# PLD_Sensors_AVR_Interface.net
KiCad netlist of a schematic drawn in Altium Designer
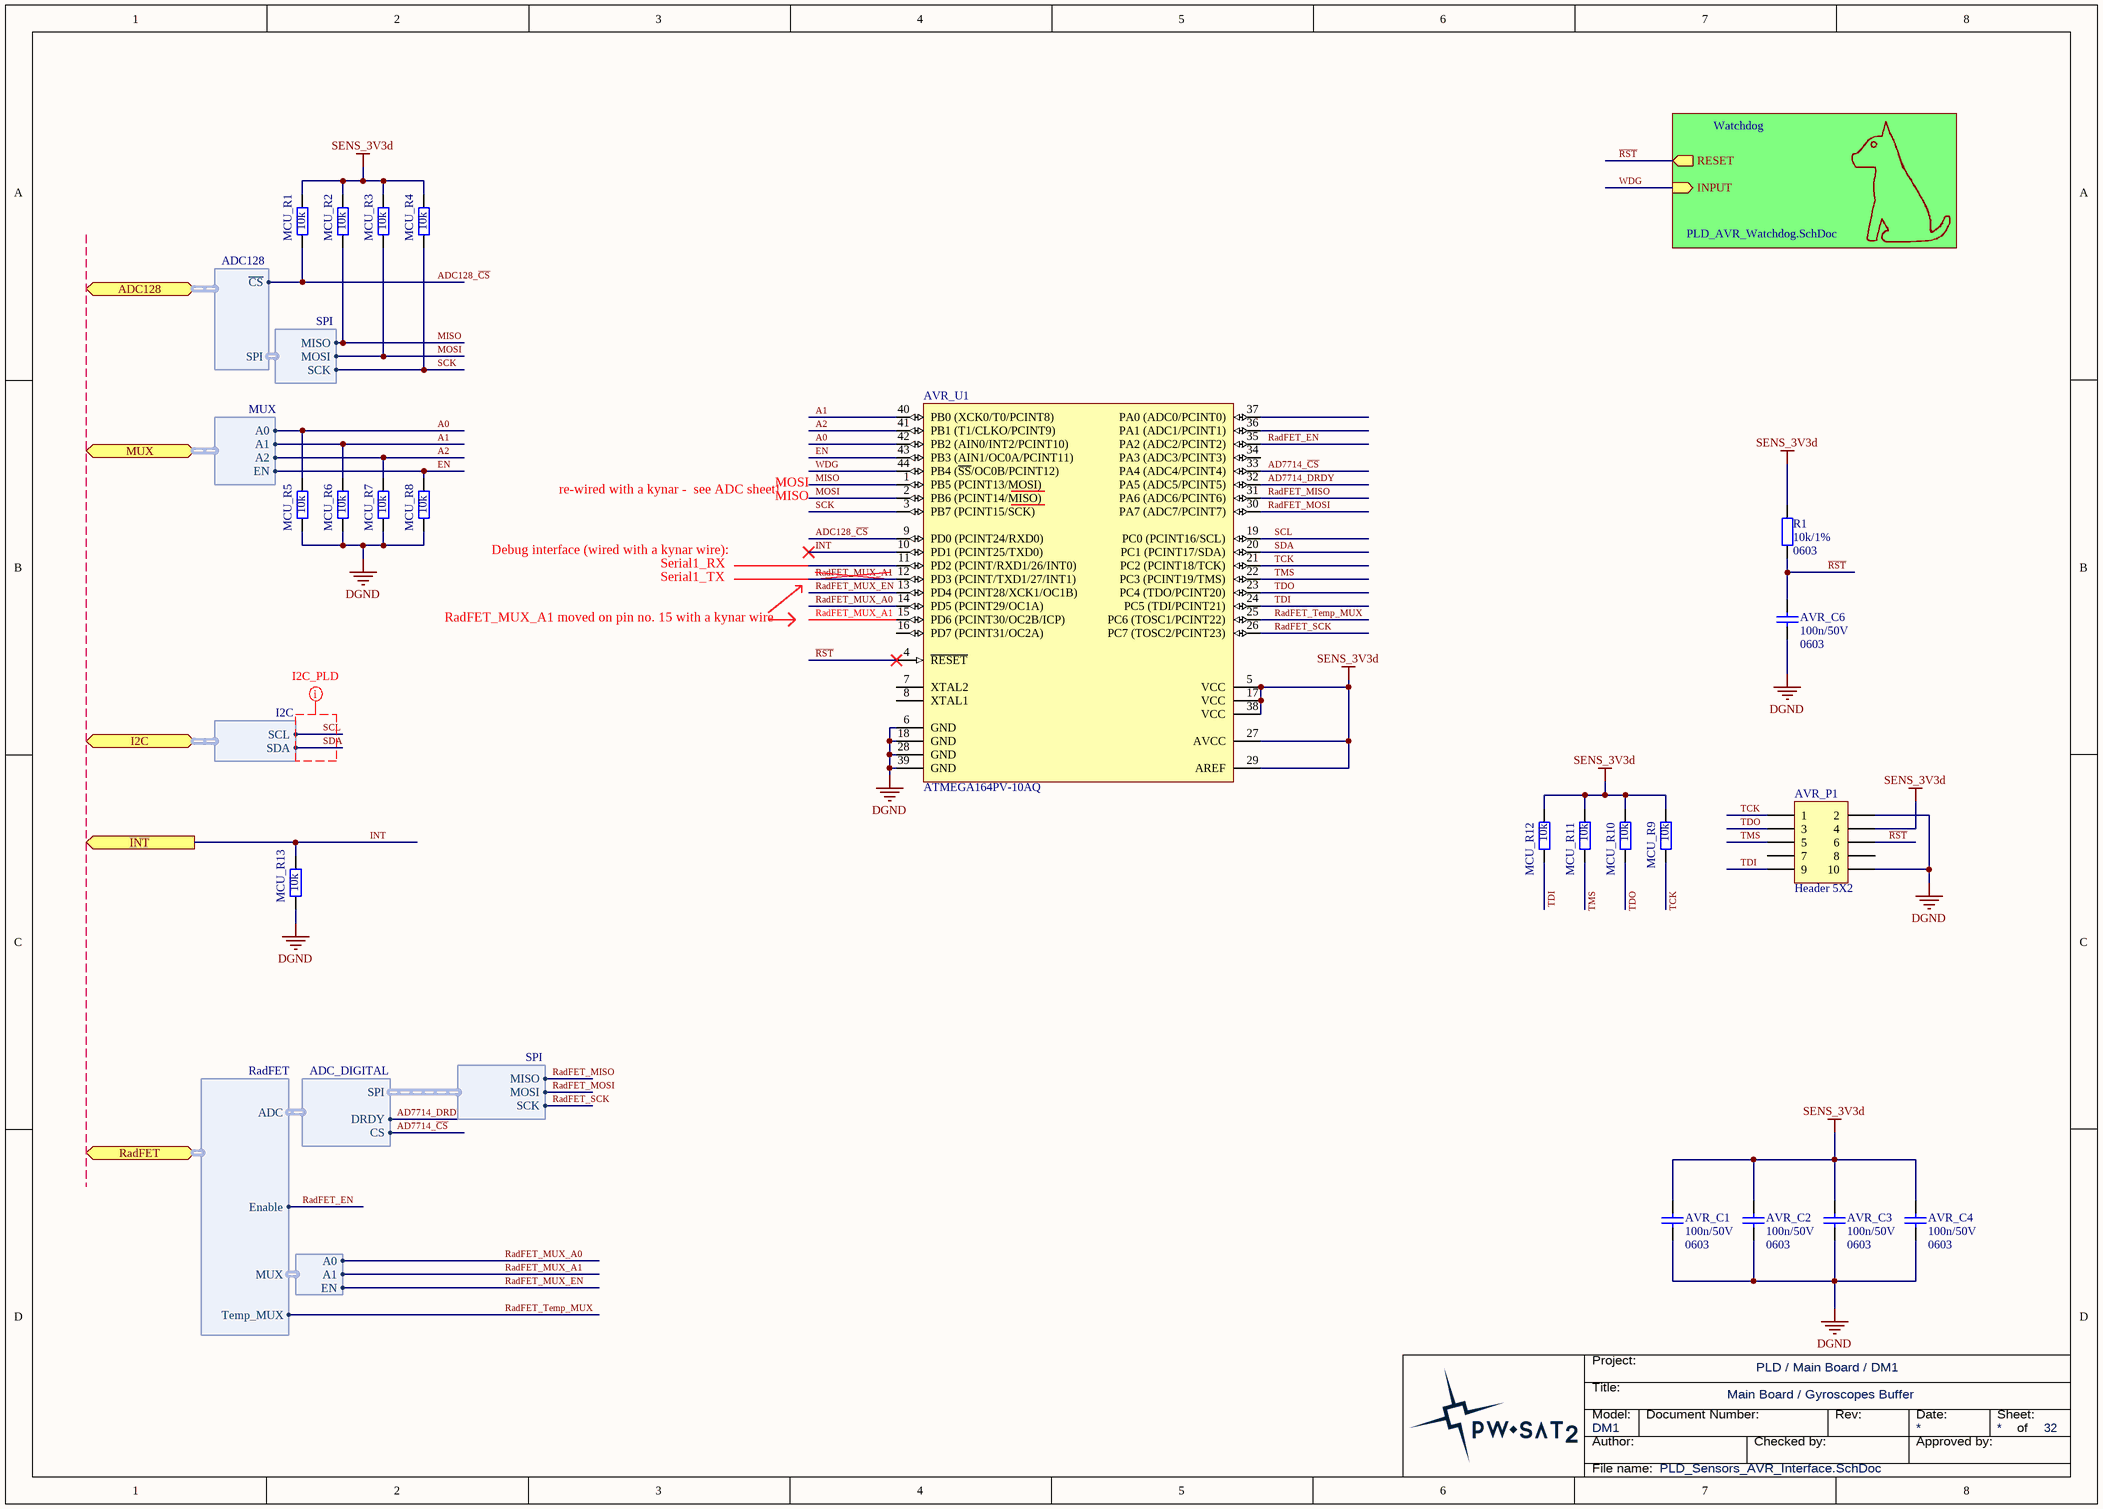
[diagram p0: PLD_Sensors_AVR_Interface.SchDoc]

(export (version "E")
  (design (tool "Eeschema 10.0.6"))
  (components
    (comp (ref "AVR_C1")
      (value "100n/50V")
      (footprint "SMD_Capacitor_0603")
      (description "Ceramic Cap Kemet COTS 100n/50V X7R 0603")
      (fields
        (field (name "MANUFACTURER") "Kemet")
        (field (name "MANUFACTURERPARTNUMBER") "C0603T104K5RALTU")
        (field (name "PACKAGE") "0603")
      )
      (libsource (lib "capacitors") (part "Cer_C0603T104K5RALTU"))
    )
    (comp (ref "AVR_C2")
      (value "100n/50V")
      (footprint "SMD_Capacitor_0603")
      (description "Ceramic Cap Kemet COTS 100n/50V X7R 0603")
      (fields
        (field (name "MANUFACTURER") "Kemet")
        (field (name "MANUFACTURERPARTNUMBER") "C0603T104K5RALTU")
        (field (name "PACKAGE") "0603")
      )
      (libsource (lib "capacitors") (part "Cer_C0603T104K5RALTU"))
    )
    (comp (ref "AVR_C3")
      (value "100n/50V")
      (footprint "SMD_Capacitor_0603")
      (description "Ceramic Cap Kemet COTS 100n/50V X7R 0603")
      (fields
        (field (name "MANUFACTURER") "Kemet")
        (field (name "MANUFACTURERPARTNUMBER") "C0603T104K5RALTU")
        (field (name "PACKAGE") "0603")
      )
      (libsource (lib "capacitors") (part "Cer_C0603T104K5RALTU"))
    )
    (comp (ref "AVR_C4")
      (value "100n/50V")
      (footprint "SMD_Capacitor_0603")
      (description "Ceramic Cap Kemet COTS 100n/50V X7R 0603")
      (fields
        (field (name "MANUFACTURER") "Kemet")
        (field (name "MANUFACTURERPARTNUMBER") "C0603T104K5RALTU")
        (field (name "PACKAGE") "0603")
      )
      (libsource (lib "capacitors") (part "Cer_C0603T104K5RALTU"))
    )
    (comp (ref "AVR_C6")
      (value "100n/50V")
      (footprint "SMD_Capacitor_0603")
      (description "Ceramic Cap Kemet COTS 100n/50V X7R 0603")
      (fields
        (field (name "MANUFACTURER") "Kemet")
        (field (name "MANUFACTURERPARTNUMBER") "C0603T104K5RALTU")
        (field (name "PACKAGE") "0603")
      )
      (libsource (lib "capacitors") (part "Cer_C0603T104K5RALTU"))
    )
    (comp (ref "AVR_P1")
      (value "Header 5X2")
      (footprint "HDR2X5")
      (description "Header, 5-Pin, Dual row")
      (fields (field (name "PUBLISHER") "Altium Limited"))
      (libsource (lib "Miscellaneous Connectors") (part "Header 5X2"))
    )
    (comp (ref "AVR_U1")
      (value "ATMEGA164PV-10AQ")
      (footprint "TQFP-44")
      (description "General-purpose microcontroller")
      (libsource (lib "microcircuits") (part "ATMEGA164PV-10AQ"))
    )
    (comp (ref "MCU_R1")
      (value "10k")
      (footprint "SMD_Resistor_0603")
      (libsource (lib "resistors") (part "Res"))
    )
    (comp (ref "MCU_R2")
      (value "10k")
      (footprint "SMD_Resistor_0603")
      (libsource (lib "resistors") (part "Res"))
    )
    (comp (ref "MCU_R3")
      (value "10k")
      (footprint "SMD_Resistor_0603")
      (libsource (lib "resistors") (part "Res"))
    )
    (comp (ref "MCU_R4")
      (value "10k")
      (footprint "SMD_Resistor_0603")
      (libsource (lib "resistors") (part "Res"))
    )
    (comp (ref "MCU_R5") (value "10k") (footprint "SMD_Resistor_0603") (libsource (lib "") (part "Res_1")))
    (comp (ref "MCU_R6") (value "10k") (footprint "SMD_Resistor_0603") (libsource (lib "") (part "Res_1")))
    (comp (ref "MCU_R7") (value "10k") (footprint "SMD_Resistor_0603") (libsource (lib "") (part "Res_1")))
    (comp (ref "MCU_R8") (value "10k") (footprint "SMD_Resistor_0603") (libsource (lib "") (part "Res_1")))
    (comp (ref "MCU_R9")
      (value "10k")
      (footprint "SMD_Resistor_0603")
      (libsource (lib "resistors") (part "Res"))
    )
    (comp (ref "MCU_R10")
      (value "10k")
      (footprint "SMD_Resistor_0603")
      (libsource (lib "resistors") (part "Res"))
    )
    (comp (ref "MCU_R11")
      (value "10k")
      (footprint "SMD_Resistor_0603")
      (libsource (lib "resistors") (part "Res"))
    )
    (comp (ref "MCU_R12")
      (value "10k")
      (footprint "SMD_Resistor_0603")
      (libsource (lib "resistors") (part "Res"))
    )
    (comp (ref "MCU_R13")
      (value "10k")
      (footprint "SMD_Resistor_0603")
      (libsource (lib "resistors") (part "Res"))
    )
    (comp (ref "R1")
      (value "10k/1%")
      (footprint "SMD_Resistor_0603")
      (description "10k/1% Vishay CRCW 0603 Resistor. 100mW, 100ppm, 75V.")
      (fields
        (field (name "MANUFACTURER") "Vishay")
        (field (name "MANUFACTURERPARTNUMBER") "CRCW060310K0FKxxxx")
        (field (name "PACKAGE") "0603")
      )
      (libsource (lib "resistors") (part "CRCW060310K0FKxxxx"))
    )
  )
  (nets
    (net (code "8") (name "/A0") (class "Default")
      (node (ref "AVR_U1") (pin "42") (pinfunction "PB2_(AIN0/INT2/PCINT10)_42") (pintype "bidirectional"))
      (node (ref "MCU_R5") (pin "2") (pinfunction "2_2") (pintype "passive"))
    )
    (net (code "9") (name "/A1") (class "Default")
      (node (ref "AVR_U1") (pin "40") (pinfunction "PB0_(XCK0/T0/PCINT8)_40") (pintype "bidirectional"))
      (node (ref "MCU_R6") (pin "2") (pinfunction "2_2") (pintype "passive"))
    )
    (net (code "10") (name "/A2") (class "Default")
      (node (ref "AVR_U1") (pin "41") (pinfunction "PB1_(T1/CLKO/PCINT9)_41") (pintype "bidirectional"))
      (node (ref "MCU_R7") (pin "2") (pinfunction "2_2") (pintype "passive"))
    )
    (net (code "11") (name "/AD7714_DRDY") (class "Default")
      (node (ref "AVR_U1") (pin "32") (pinfunction "PA5_(ADC5/PCINT5)_32") (pintype "bidirectional"))
    )
    (net (code "12") (name "/AD7714_~{CS}") (class "Default")
      (node (ref "AVR_U1") (pin "33") (pinfunction "PA4_(ADC4/PCINT4)_33") (pintype "bidirectional"))
    )
    (net (code "13") (name "/ADC128_~{CS}") (class "Default")
      (node (ref "AVR_U1") (pin "9") (pinfunction "PD0_(PCINT24/RXD0)_9") (pintype "bidirectional"))
      (node (ref "MCU_R1") (pin "2") (pinfunction "2_2") (pintype "passive"))
    )
    (net (code "15") (name "/EN") (class "Default")
      (node (ref "AVR_U1") (pin "43") (pinfunction "PB3_(AIN1/OC0A/PCINT11)_43") (pintype "bidirectional"))
      (node (ref "MCU_R8") (pin "2") (pinfunction "2_2") (pintype "passive"))
    )
    (net (code "16") (name "/INT") (class "Default")
      (node (ref "AVR_U1") (pin "10") (pinfunction "PD1_(PCINT25/TXD0)_10") (pintype "bidirectional"))
      (node (ref "MCU_R13") (pin "1") (pinfunction "1_1") (pintype "passive"))
    )
    (net (code "17") (name "/MISO") (class "Default")
      (node (ref "AVR_U1") (pin "1") (pinfunction "PB5_(PCINT13/MOSI)_1") (pintype "bidirectional"))
      (node (ref "MCU_R2") (pin "2") (pinfunction "2_2") (pintype "passive"))
    )
    (net (code "18") (name "/MOSI") (class "Default")
      (node (ref "AVR_U1") (pin "2") (pinfunction "PB6_(PCINT14/MISO)_2") (pintype "bidirectional"))
      (node (ref "MCU_R3") (pin "2") (pinfunction "2_2") (pintype "passive"))
    )
    (net (code "19") (name "/RadFET_EN") (class "Default")
      (node (ref "AVR_U1") (pin "35") (pinfunction "PA2_(ADC2/PCINT2)_35") (pintype "bidirectional"))
    )
    (net (code "20") (name "/RadFET_MISO") (class "Default")
      (node (ref "AVR_U1") (pin "31") (pinfunction "PA6_(ADC6/PCINT6)_31") (pintype "bidirectional"))
    )
    (net (code "21") (name "/RadFET_MOSI") (class "Default")
      (node (ref "AVR_U1") (pin "30") (pinfunction "PA7_(ADC7/PCINT7)_30") (pintype "bidirectional"))
    )
    (net (code "22") (name "/RadFET_MUX_A0") (class "Default")
      (node (ref "AVR_U1") (pin "14") (pinfunction "PD5_(PCINT29/OC1A)_14") (pintype "bidirectional"))
    )
    (net (code "23") (name "/RadFET_MUX_A1") (class "Default")
      (node (ref "AVR_U1") (pin "12") (pinfunction "PD3_(PCINT/TXD1/27/INT1)_12") (pintype "bidirectional"))
    )
    (net (code "24") (name "/RadFET_MUX_EN") (class "Default")
      (node (ref "AVR_U1") (pin "13") (pinfunction "PD4_(PCINT28/XCK1/OC1B)_13") (pintype "bidirectional"))
    )
    (net (code "25") (name "/RadFET_SCK") (class "Default")
      (node (ref "AVR_U1") (pin "26") (pinfunction "PC7_(TOSC2/PCINT23)_26") (pintype "bidirectional"))
    )
    (net (code "26") (name "/RadFET_Temp_MUX") (class "Default")
      (node (ref "AVR_U1") (pin "25") (pinfunction "PC6_(TOSC1/PCINT22)_25") (pintype "bidirectional"))
    )
    (net (code "28") (name "/SCK") (class "Default")
      (node (ref "AVR_U1") (pin "3") (pinfunction "PB7_(PCINT15/SCK)_3") (pintype "bidirectional"))
      (node (ref "MCU_R4") (pin "2") (pinfunction "2_2") (pintype "passive"))
    )
    (net (code "29") (name "/SCL") (class "Default")
      (node (ref "AVR_U1") (pin "19") (pinfunction "PC0_(PCINT16/SCL)_19") (pintype "bidirectional"))
    )
    (net (code "30") (name "/SDA") (class "Default")
      (node (ref "AVR_U1") (pin "20") (pinfunction "PC1_(PCINT17/SDA)_20") (pintype "bidirectional"))
    )
    (net (code "31") (name "/TCK") (class "Default")
      (node (ref "AVR_P1") (pin "1") (pinfunction "1_1") (pintype "passive"))
      (node (ref "AVR_U1") (pin "21") (pinfunction "PC2_(PCINT18/TCK)_21") (pintype "bidirectional"))
      (node (ref "MCU_R9") (pin "2") (pinfunction "2_2") (pintype "passive"))
    )
    (net (code "32") (name "/TDI") (class "Default")
      (node (ref "AVR_P1") (pin "9") (pinfunction "9_9") (pintype "passive"))
      (node (ref "AVR_U1") (pin "24") (pinfunction "PC5_(TDI/PCINT21)_24") (pintype "bidirectional"))
      (node (ref "MCU_R12") (pin "2") (pinfunction "2_2") (pintype "passive"))
    )
    (net (code "33") (name "/TDO") (class "Default")
      (node (ref "AVR_P1") (pin "3") (pinfunction "3_3") (pintype "passive"))
      (node (ref "AVR_U1") (pin "23") (pinfunction "PC4_(TDO/PCINT20)_23") (pintype "bidirectional"))
      (node (ref "MCU_R10") (pin "2") (pinfunction "2_2") (pintype "passive"))
    )
    (net (code "34") (name "/TMS") (class "Default")
      (node (ref "AVR_P1") (pin "5") (pinfunction "5_5") (pintype "passive"))
      (node (ref "AVR_U1") (pin "22") (pinfunction "PC3_(PCINT19/TMS)_22") (pintype "bidirectional"))
      (node (ref "MCU_R11") (pin "2") (pinfunction "2_2") (pintype "passive"))
    )
    (net (code "35") (name "/WDG") (class "Default")
      (node (ref "AVR_U1") (pin "44") (pinfunction "PB4_(~{SS}/OC0B/PCINT12)_44") (pintype "bidirectional"))
    )
    (net (code "41") (name "/~{RST}") (class "Default")
      (node (ref "AVR_C6") (pin "1") (pinfunction "1_1") (pintype "passive"))
      (node (ref "AVR_P1") (pin "6") (pinfunction "6_6") (pintype "passive"))
      (node (ref "AVR_U1") (pin "4") (pinfunction "~{RESET}_4") (pintype "input"))
      (node (ref "R1") (pin "2") (pinfunction "2_2") (pintype "passive"))
    )
    (net (code "42") (name "DGND") (class "Default")
      (node (ref "AVR_C1") (pin "2") (pinfunction "2_2") (pintype "passive"))
      (node (ref "AVR_C2") (pin "2") (pinfunction "2_2") (pintype "passive"))
      (node (ref "AVR_C3") (pin "2") (pinfunction "2_2") (pintype "passive"))
      (node (ref "AVR_C4") (pin "2") (pinfunction "2_2") (pintype "passive"))
      (node (ref "AVR_C6") (pin "2") (pinfunction "2_2") (pintype "passive"))
      (node (ref "AVR_P1") (pin "10") (pinfunction "10_10") (pintype "passive"))
      (node (ref "AVR_P1") (pin "2") (pinfunction "2_2") (pintype "passive"))
      (node (ref "AVR_U1") (pin "18") (pinfunction "GND_18") (pintype "power_in"))
      (node (ref "AVR_U1") (pin "28") (pinfunction "GND_28") (pintype "power_in"))
      (node (ref "AVR_U1") (pin "39") (pinfunction "GND_39") (pintype "power_in"))
      (node (ref "AVR_U1") (pin "6") (pinfunction "GND_6") (pintype "power_in"))
      (node (ref "MCU_R13") (pin "2") (pinfunction "2_2") (pintype "passive"))
      (node (ref "MCU_R5") (pin "1") (pinfunction "1_1") (pintype "passive"))
      (node (ref "MCU_R6") (pin "1") (pinfunction "1_1") (pintype "passive"))
      (node (ref "MCU_R7") (pin "1") (pinfunction "1_1") (pintype "passive"))
      (node (ref "MCU_R8") (pin "1") (pinfunction "1_1") (pintype "passive"))
    )
    (net (code "43") (name "SENS_3V3d") (class "Default")
      (node (ref "AVR_C1") (pin "1") (pinfunction "1_1") (pintype "passive"))
      (node (ref "AVR_C2") (pin "1") (pinfunction "1_1") (pintype "passive"))
      (node (ref "AVR_C3") (pin "1") (pinfunction "1_1") (pintype "passive"))
      (node (ref "AVR_C4") (pin "1") (pinfunction "1_1") (pintype "passive"))
      (node (ref "AVR_P1") (pin "4") (pinfunction "4_4") (pintype "passive"))
      (node (ref "AVR_U1") (pin "17") (pinfunction "VCC_17") (pintype "power_in"))
      (node (ref "AVR_U1") (pin "27") (pinfunction "AVCC_27") (pintype "power_in"))
      (node (ref "AVR_U1") (pin "29") (pinfunction "AREF_29") (pintype "power_in"))
      (node (ref "AVR_U1") (pin "38") (pinfunction "VCC_38") (pintype "power_in"))
      (node (ref "AVR_U1") (pin "5") (pinfunction "VCC_5") (pintype "power_in"))
      (node (ref "MCU_R1") (pin "1") (pinfunction "1_1") (pintype "passive"))
      (node (ref "MCU_R10") (pin "1") (pinfunction "1_1") (pintype "passive"))
      (node (ref "MCU_R11") (pin "1") (pinfunction "1_1") (pintype "passive"))
      (node (ref "MCU_R12") (pin "1") (pinfunction "1_1") (pintype "passive"))
      (node (ref "MCU_R2") (pin "1") (pinfunction "1_1") (pintype "passive"))
      (node (ref "MCU_R3") (pin "1") (pinfunction "1_1") (pintype "passive"))
      (node (ref "MCU_R4") (pin "1") (pinfunction "1_1") (pintype "passive"))
      (node (ref "MCU_R9") (pin "1") (pinfunction "1_1") (pintype "passive"))
      (node (ref "R1") (pin "1") (pinfunction "1_1") (pintype "passive"))
    )
    (net (code "44") (name "unconnected-(AVR_P1-Pad7)") (class "Default")
      (node (ref "AVR_P1") (pin "7") (pinfunction "7_7") (pintype "passive"))
    )
    (net (code "45") (name "unconnected-(AVR_P1-Pad8)") (class "Default")
      (node (ref "AVR_P1") (pin "8") (pinfunction "8_8") (pintype "passive"))
    )
    (net (code "46") (name "unconnected-(AVR_U1-PA0_(ADC0{slash}PCINT0)-Pad37)") (class "Default")
      (node (ref "AVR_U1") (pin "37") (pinfunction "PA0_(ADC0/PCINT0)_37") (pintype "bidirectional"))
    )
    (net (code "47") (name "unconnected-(AVR_U1-PA1_(ADC1{slash}PCINT1)-Pad36)") (class "Default")
      (node (ref "AVR_U1") (pin "36") (pinfunction "PA1_(ADC1/PCINT1)_36") (pintype "bidirectional"))
    )
    (net (code "48") (name "unconnected-(AVR_U1-PA3_(ADC3{slash}PCINT3)-Pad34)") (class "Default")
      (node (ref "AVR_U1") (pin "34") (pinfunction "PA3_(ADC3/PCINT3)_34") (pintype "bidirectional"))
    )
    (net (code "49") (name "unconnected-(AVR_U1-PD2_(PCINT{slash}RXD1{slash}26{slash}INT0)-Pad11)") (class "Default")
      (node (ref "AVR_U1") (pin "11") (pinfunction "PD2_(PCINT/RXD1/26/INT0)_11") (pintype "bidirectional"))
    )
    (net (code "50") (name "unconnected-(AVR_U1-PD6_(PCINT30{slash}OC2B{slash}ICP)-Pad15)") (class "Default")
      (node (ref "AVR_U1") (pin "15") (pinfunction "PD6_(PCINT30/OC2B/ICP)_15") (pintype "bidirectional"))
    )
    (net (code "51") (name "unconnected-(AVR_U1-PD7_(PCINT31{slash}OC2A)-Pad16)") (class "Default")
      (node (ref "AVR_U1") (pin "16") (pinfunction "PD7_(PCINT31/OC2A)_16") (pintype "bidirectional"))
    )
    (net (code "52") (name "unconnected-(AVR_U1-XTAL1-Pad8)") (class "Default")
      (node (ref "AVR_U1") (pin "8") (pinfunction "XTAL1_8") (pintype "passive"))
    )
    (net (code "53") (name "unconnected-(AVR_U1-XTAL2-Pad7)") (class "Default")
      (node (ref "AVR_U1") (pin "7") (pinfunction "XTAL2_7") (pintype "passive"))
    )
  )
)
